# linearSensor.net
KiCad netlist of a schematic drawn in EAGLE
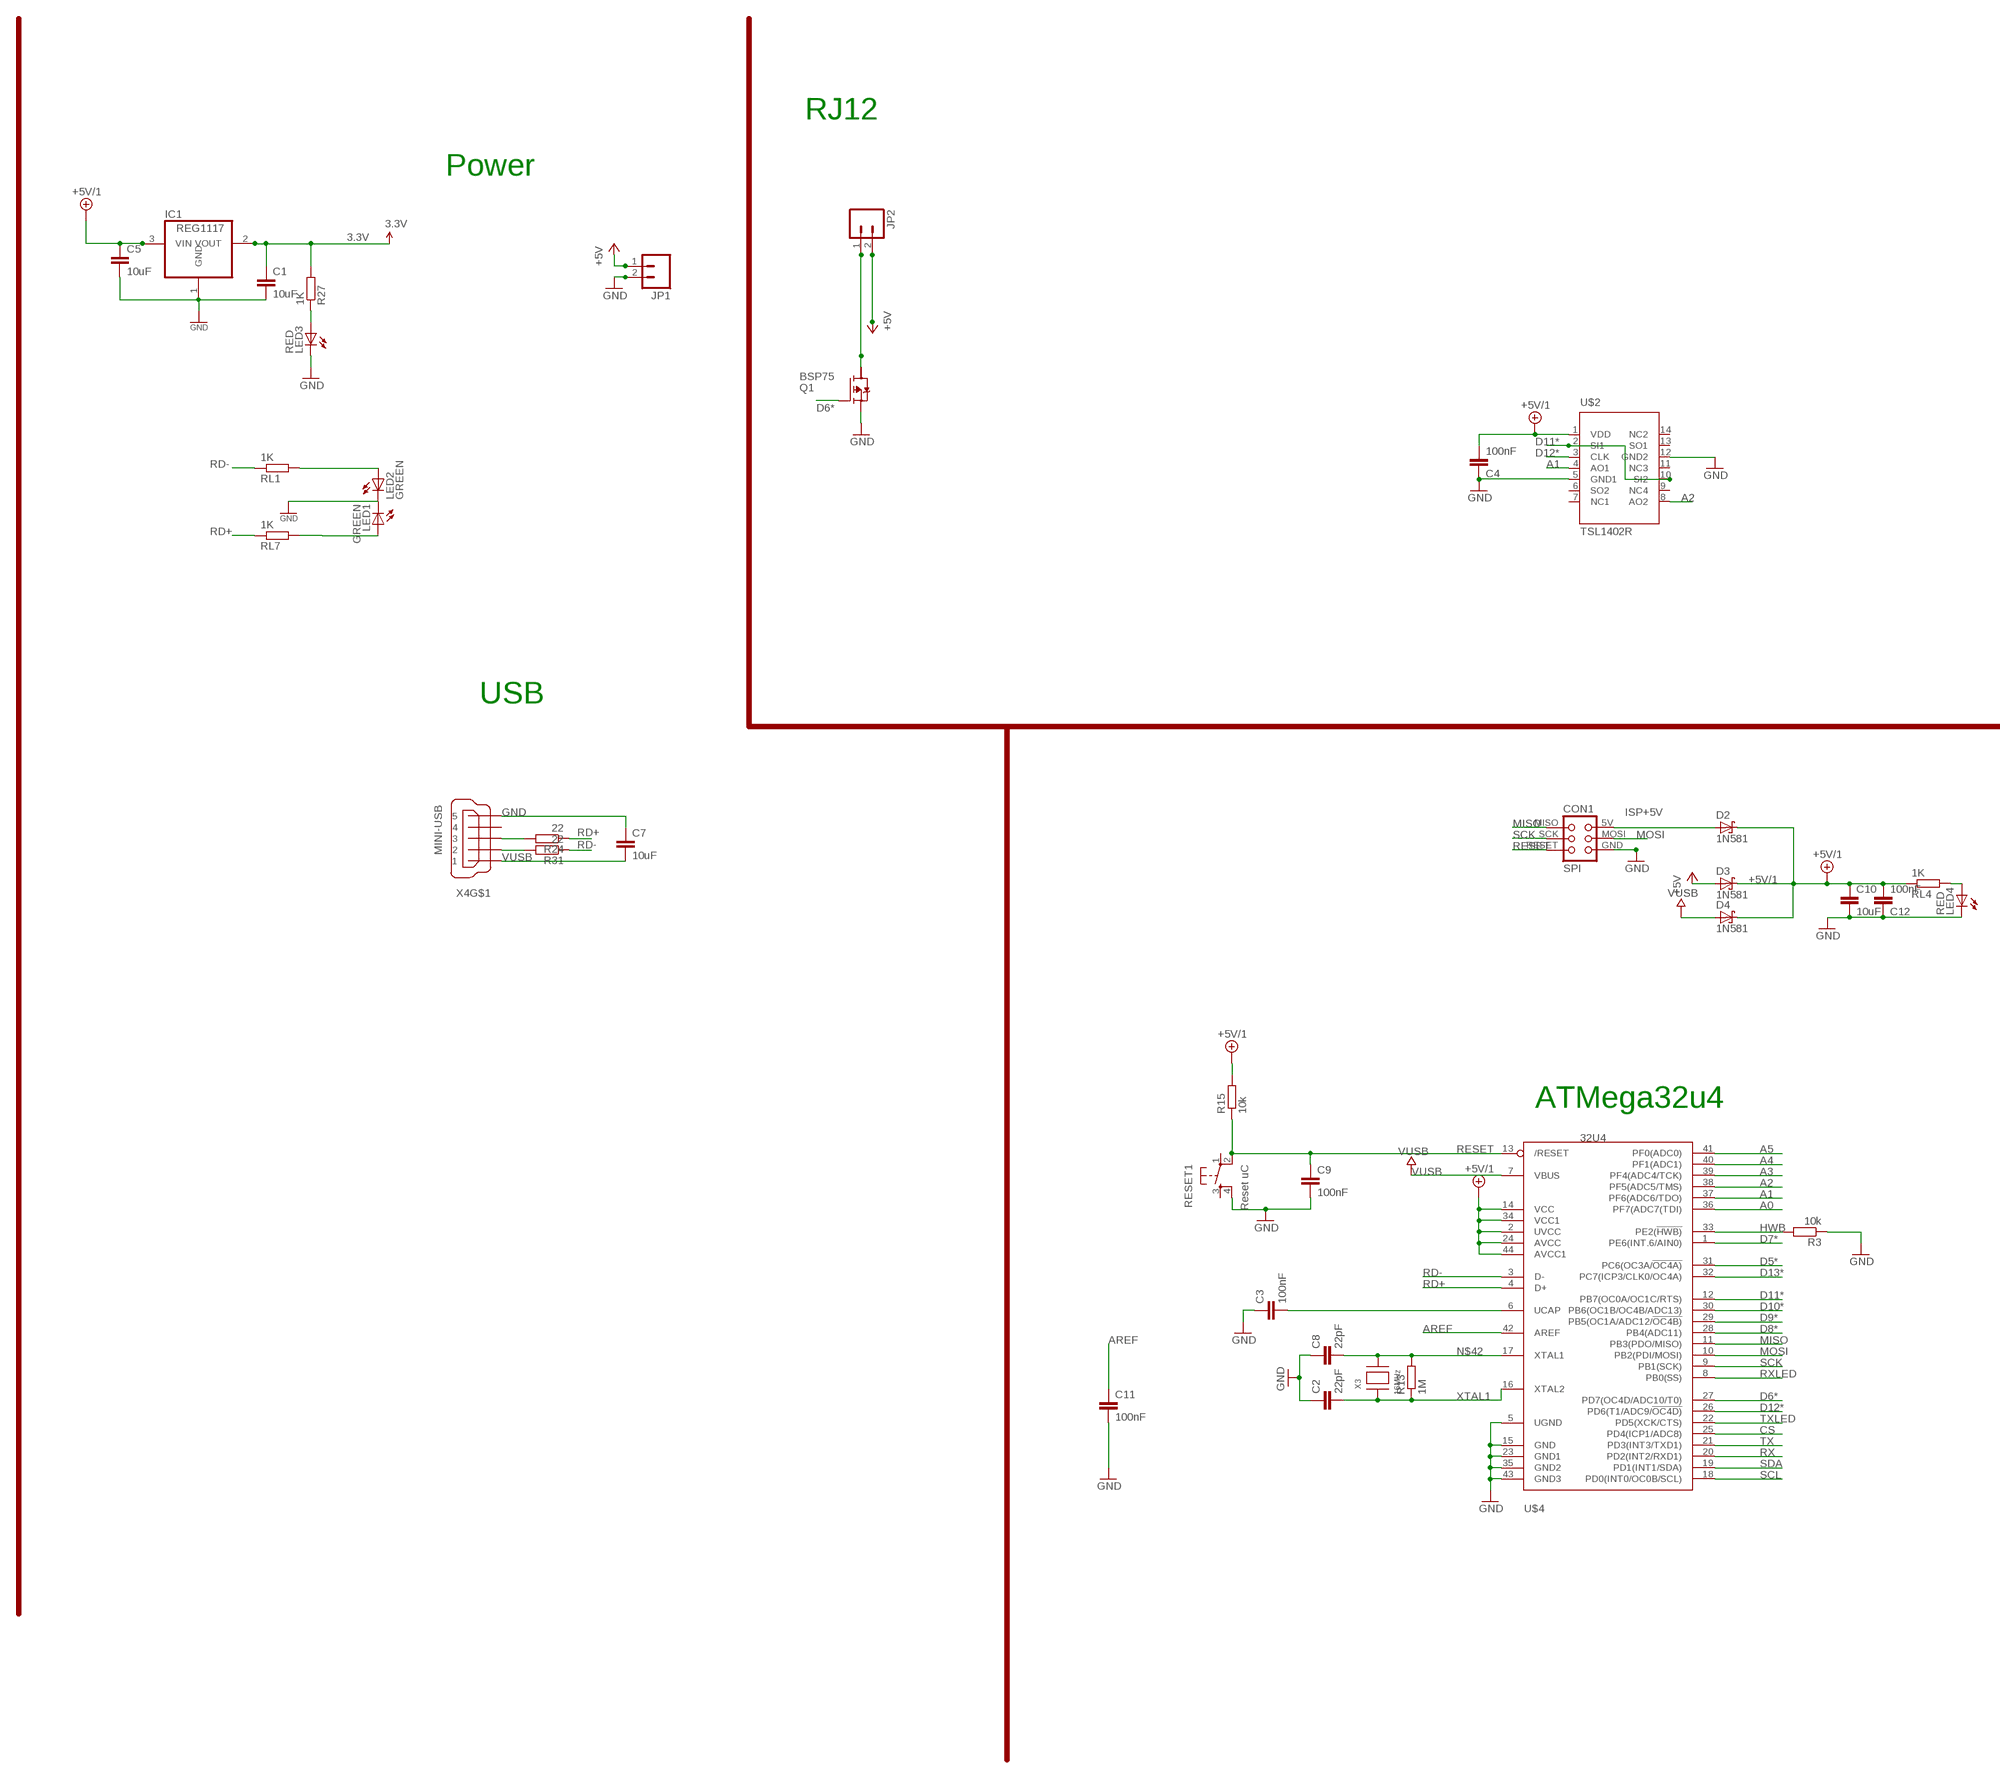
[diagram p0: schematic, sheet 1, part 1 of 2]
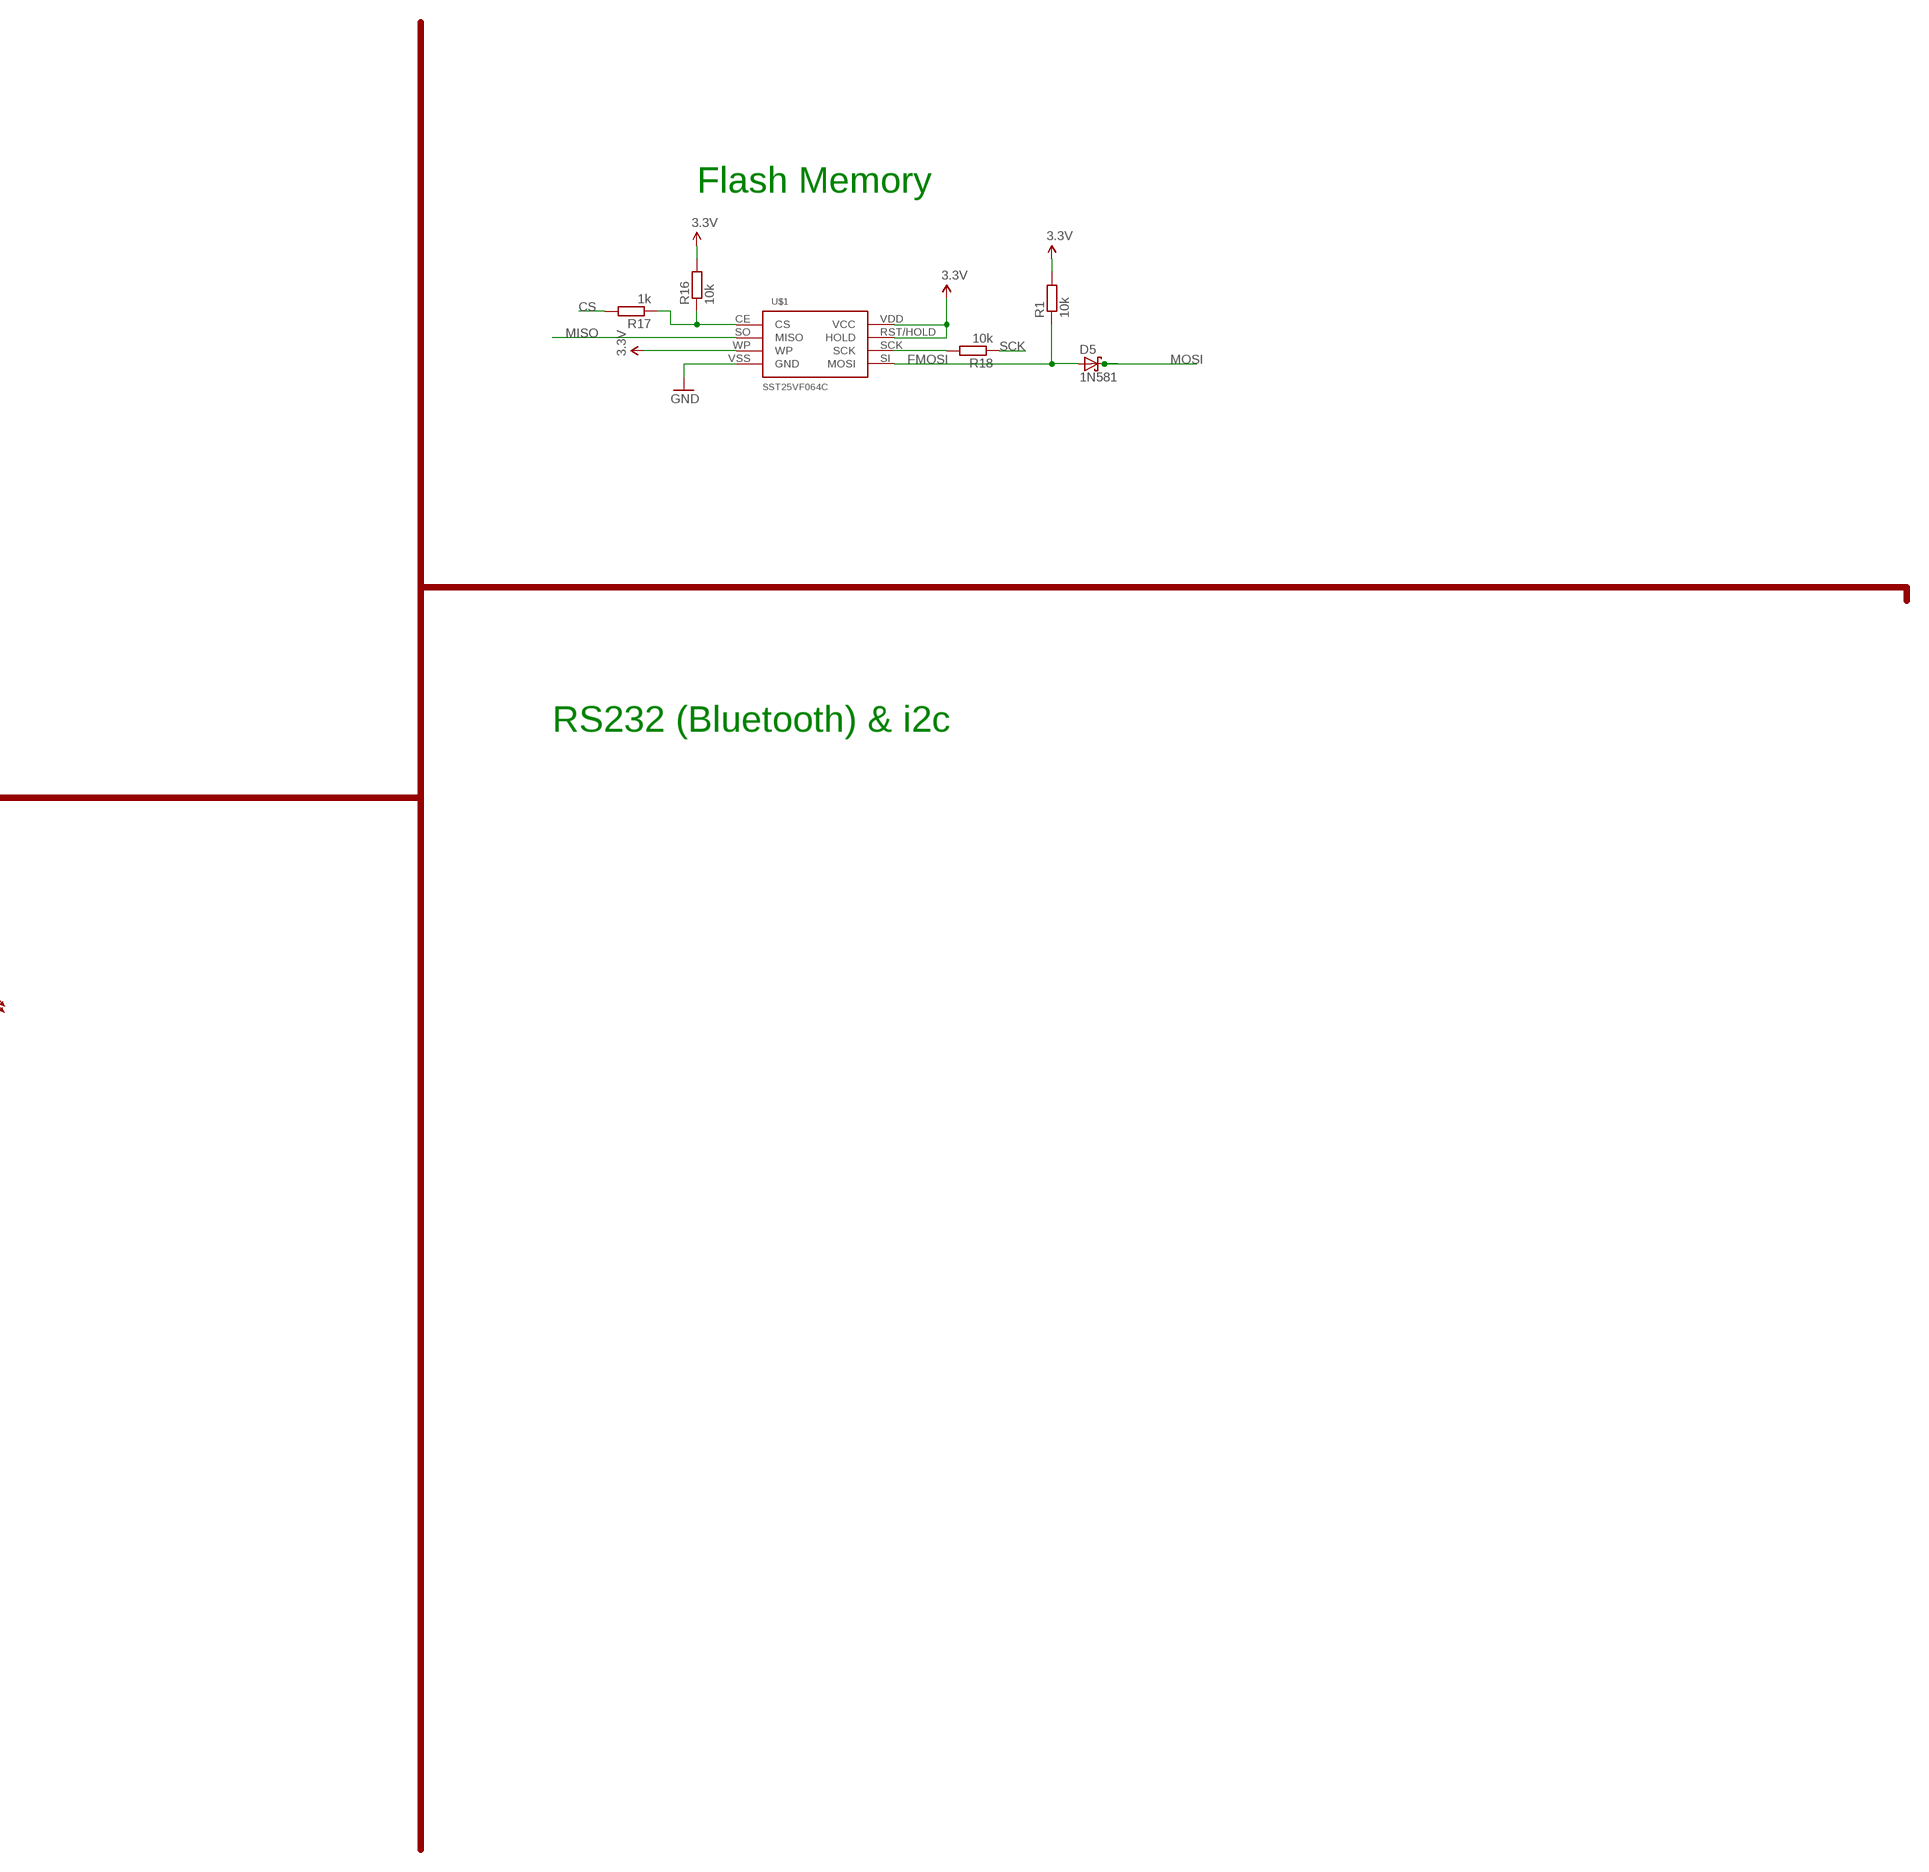
[diagram p1: schematic, sheet 1, part 2 of 2]

(export (version "E")
  (design (tool "Eeschema 10.0.6"))
  (components
    (comp (ref "C1")
      (value "10uF")
      (footprint "eagle-import:C1206")
      (libsource (lib "eagle-import") (part "C-EUC1206"))
    )
    (comp (ref "C2")
      (value "22pF")
      (footprint "eagle-import:C1206")
      (libsource (lib "eagle-import") (part "C-EUC1206"))
    )
    (comp (ref "C3")
      (value "100nF")
      (footprint "eagle-import:C1206")
      (libsource (lib "eagle-import") (part "C-EUC1206"))
    )
    (comp (ref "C4")
      (value "100nF")
      (footprint "eagle-import:C1206")
      (libsource (lib "eagle-import") (part "C-EUC1206"))
    )
    (comp (ref "C5")
      (value "10uF")
      (footprint "eagle-import:C1206")
      (libsource (lib "eagle-import") (part "C-EUC1206"))
    )
    (comp (ref "C7")
      (value "10uF")
      (footprint "eagle-import:C1206")
      (libsource (lib "eagle-import") (part "C-EUC1206"))
    )
    (comp (ref "C8")
      (value "22pF")
      (footprint "eagle-import:C1206")
      (libsource (lib "eagle-import") (part "C-EUC1206"))
    )
    (comp (ref "C9")
      (value "100nF")
      (footprint "eagle-import:C1206")
      (libsource (lib "eagle-import") (part "C-EUC1206"))
    )
    (comp (ref "C10")
      (value "10uF")
      (footprint "eagle-import:C1206")
      (libsource (lib "eagle-import") (part "C-EUC1206"))
    )
    (comp (ref "C11")
      (value "100nF")
      (footprint "eagle-import:C1206")
      (libsource (lib "eagle-import") (part "C-EUC1206"))
    )
    (comp (ref "C12")
      (value "100nF")
      (footprint "eagle-import:C1206")
      (libsource (lib "eagle-import") (part "C-EUC1206"))
    )
    (comp (ref "CON1")
      (value "SPI")
      (footprint "eagle-import:TC2030-MCP-NL")
      (libsource (lib "eagle-import") (part "TINYISPT"))
    )
    (comp (ref "D2")
      (value "1N581")
      (footprint "eagle-import:LED-1206")
      (libsource (lib "eagle-import") (part "1N581D1206"))
    )
    (comp (ref "D3")
      (value "1N581")
      (footprint "eagle-import:LED-1206")
      (libsource (lib "eagle-import") (part "1N581D1206"))
    )
    (comp (ref "D4")
      (value "1N581")
      (footprint "eagle-import:LED-1206")
      (libsource (lib "eagle-import") (part "1N581D1206"))
    )
    (comp (ref "D5")
      (value "1N581")
      (footprint "eagle-import:LED-1206")
      (libsource (lib "eagle-import") (part "1N581D1206"))
    )
    (comp (ref "IC1")
      (value "REG1117")
      (footprint "eagle-import:SOT223")
      (libsource (lib "eagle-import") (part "REG1117"))
    )
    (comp (ref "JP1")
      (value "M02LOCK_LONGPADS")
      (footprint "eagle-import:1X02_LOCK_LONGPADS")
      (libsource (lib "eagle-import") (part "M02LOCK_LONGPADS"))
    )
    (comp (ref "JP2")
      (value "M02LOCK_LONGPADS")
      (footprint "eagle-import:1X02_LOCK_LONGPADS")
      (libsource (lib "eagle-import") (part "M02LOCK_LONGPADS"))
    )
    (comp (ref "LED1")
      (value "GREEN")
      (footprint "eagle-import:CHIP-LED0805")
      (libsource (lib "eagle-import") (part "LEDCHIP-LED0805"))
    )
    (comp (ref "LED2")
      (value "GREEN")
      (footprint "eagle-import:CHIP-LED0805")
      (libsource (lib "eagle-import") (part "LEDCHIP-LED0805"))
    )
    (comp (ref "LED3")
      (value "RED")
      (footprint "eagle-import:CHIP-LED0805")
      (libsource (lib "eagle-import") (part "LEDCHIP-LED0805"))
    )
    (comp (ref "LED4")
      (value "RED")
      (footprint "eagle-import:CHIP-LED0805")
      (libsource (lib "eagle-import") (part "LEDCHIP-LED0805"))
    )
    (comp (ref "Q1")
      (value "BSP75")
      (footprint "eagle-import:PG-SOT-223")
      (libsource (lib "eagle-import") (part "BSP613P"))
    )
    (comp (ref "R1")
      (value "10k")
      (footprint "eagle-import:R1206")
      (libsource (lib "eagle-import") (part "R-EU_R1206"))
    )
    (comp (ref "R3")
      (value "10k")
      (footprint "eagle-import:M0805")
      (libsource (lib "eagle-import") (part "resistor_R-EU_M0805"))
    )
    (comp (ref "R13")
      (value "1M")
      (footprint "eagle-import:R1206")
      (libsource (lib "eagle-import") (part "R-EU_R1206"))
    )
    (comp (ref "R15")
      (value "10k")
      (footprint "eagle-import:M0805")
      (libsource (lib "eagle-import") (part "resistor_R-EU_M0805"))
    )
    (comp (ref "R16")
      (value "10k")
      (footprint "eagle-import:R1206")
      (libsource (lib "eagle-import") (part "R-EU_R1206"))
    )
    (comp (ref "R17")
      (value "1k")
      (footprint "eagle-import:R0805")
      (libsource (lib "eagle-import") (part "R-EU_R0805"))
    )
    (comp (ref "R18")
      (value "10k")
      (footprint "eagle-import:R1206")
      (libsource (lib "eagle-import") (part "R-EU_R1206"))
    )
    (comp (ref "R24")
      (value "22")
      (footprint "eagle-import:M1206")
      (libsource (lib "eagle-import") (part "resistor_R-EU_M1206"))
    )
    (comp (ref "R27")
      (value "1K")
      (footprint "eagle-import:R0805")
      (libsource (lib "eagle-import") (part "R-EU_R0805"))
    )
    (comp (ref "R31")
      (value "22")
      (footprint "eagle-import:M1206")
      (libsource (lib "eagle-import") (part "resistor_R-EU_M1206"))
    )
    (comp (ref "RESET1")
      (value "Reset uC")
      (footprint "eagle-import:TACTILE_SWITCH_SMD")
      (libsource (lib "eagle-import") (part "TAC_SWITCHSMD"))
    )
    (comp (ref "RL1")
      (value "1K")
      (footprint "eagle-import:R0805")
      (libsource (lib "eagle-import") (part "R-EU_R0805"))
    )
    (comp (ref "RL4")
      (value "1K")
      (footprint "eagle-import:R0805")
      (libsource (lib "eagle-import") (part "resistor_R-EU_R0805"))
    )
    (comp (ref "RL7")
      (value "1K")
      (footprint "eagle-import:R0805")
      (libsource (lib "eagle-import") (part "R-EU_R0805"))
    )
    (comp (ref "U$1")
      (value "SST25VF064C")
      (footprint "eagle-import:SOIC_8-LEAD")
      (libsource (lib "eagle-import") (part "SST25VF064C"))
    )
    (comp (ref "U$2")
      (value "TSL1402R")
      (footprint "eagle-import:DIL14")
      (libsource (lib "eagle-import") (part "TSL1402R"))
    )
    (comp (ref "U$4")
      (value "32U4")
      (footprint "eagle-import:TQFP44")
      (libsource (lib "eagle-import") (part "ATMEGA32U4-AU"))
    )
    (comp (ref "X3")
      (value "16MHz")
      (footprint "eagle-import:NX6035")
      (libsource (lib "eagle-import") (part "XTALNX6035"))
    )
    (comp (ref "X4")
      (value "MINI-USB")
      (footprint "eagle-import:32005-201")
      (libsource (lib "eagle-import") (part "MINI-USB-SCHIELD-32005-201"))
    )
  )
  (nets
    (net (code "1") (name "+5V") (class "Default")
      (node (ref "D3") (pin "A") (pinfunction "A_A") (pintype "passive"))
      (node (ref "JP1") (pin "1") (pinfunction "1_1") (pintype "passive"))
      (node (ref "JP2") (pin "2") (pinfunction "2_2") (pintype "passive"))
    )
    (net (code "2") (name "+5V{slash}1") (class "Default")
      (node (ref "C10") (pin "1") (pinfunction "1_1") (pintype "passive"))
      (node (ref "C12") (pin "2") (pinfunction "2_2") (pintype "passive"))
      (node (ref "C4") (pin "2") (pinfunction "2_2") (pintype "passive"))
      (node (ref "C5") (pin "1") (pinfunction "1_1") (pintype "passive"))
      (node (ref "D2") (pin "C") (pinfunction "C_C") (pintype "passive"))
      (node (ref "D3") (pin "C") (pinfunction "C_C") (pintype "passive"))
      (node (ref "D4") (pin "C") (pinfunction "C_C") (pintype "passive"))
      (node (ref "IC1") (pin "3") (pinfunction "VIN_3") (pintype "input"))
      (node (ref "R15") (pin "2") (pinfunction "2_2") (pintype "passive"))
      (node (ref "RL4") (pin "1") (pinfunction "1_1") (pintype "passive"))
      (node (ref "U$2") (pin "1") (pinfunction "VDD_1") (pintype "power_in"))
      (node (ref "U$4") (pin "14") (pinfunction "VCC_14") (pintype "bidirectional"))
      (node (ref "U$4") (pin "2") (pinfunction "UVCC_2") (pintype "bidirectional"))
      (node (ref "U$4") (pin "24") (pinfunction "AVCC_24") (pintype "bidirectional"))
      (node (ref "U$4") (pin "34") (pinfunction "VCC1_34") (pintype "bidirectional"))
      (node (ref "U$4") (pin "44") (pinfunction "AVCC1_44") (pintype "bidirectional"))
    )
    (net (code "3") (name "/A0") (class "Default")
      (node (ref "U$4") (pin "36") (pinfunction "PF7(ADC7(TDI)_36") (pintype "bidirectional"))
    )
    (net (code "4") (name "/A1") (class "Default")
      (node (ref "U$2") (pin "4") (pinfunction "AO1_4") (pintype "output"))
      (node (ref "U$4") (pin "37") (pinfunction "PF6(ADC6/TDO)_37") (pintype "bidirectional"))
    )
    (net (code "5") (name "/A2") (class "Default")
      (node (ref "U$2") (pin "8") (pinfunction "AO2_8") (pintype "output"))
      (node (ref "U$4") (pin "38") (pinfunction "PF5(ADC5/TMS)_38") (pintype "bidirectional"))
    )
    (net (code "6") (name "/A3") (class "Default")
      (node (ref "U$4") (pin "39") (pinfunction "PF4(ADC4/TCK)_39") (pintype "bidirectional"))
    )
    (net (code "7") (name "/A4") (class "Default")
      (node (ref "U$4") (pin "40") (pinfunction "PF1(ADC1)_40") (pintype "bidirectional"))
    )
    (net (code "8") (name "/A5") (class "Default")
      (node (ref "U$4") (pin "41") (pinfunction "PF0(ADC0)_41") (pintype "bidirectional"))
    )
    (net (code "9") (name "/AREF") (class "Default")
      (node (ref "C11") (pin "1") (pinfunction "1_1") (pintype "passive"))
      (node (ref "U$4") (pin "42") (pinfunction "AREF_42") (pintype "bidirectional"))
    )
    (net (code "10") (name "/CS") (class "Default")
      (node (ref "R17") (pin "2") (pinfunction "2_2") (pintype "passive"))
      (node (ref "U$4") (pin "25") (pinfunction "PD4(ICP1/ADC8)_25") (pintype "bidirectional"))
    )
    (net (code "11") (name "/D5*") (class "Default")
      (node (ref "U$4") (pin "31") (pinfunction "PC6(OC3A/~{OC4A})_31") (pintype "bidirectional"))
    )
    (net (code "12") (name "/D6*") (class "Default")
      (node (ref "Q1") (pin "1") (pinfunction "G_1") (pintype "passive"))
      (node (ref "U$4") (pin "27") (pinfunction "PD7(OC4D/ADC10/T0)_27") (pintype "bidirectional"))
    )
    (net (code "13") (name "/D7*") (class "Default")
      (node (ref "U$4") (pin "1") (pinfunction "PE6(INT.6/AIN0)_1") (pintype "bidirectional"))
    )
    (net (code "14") (name "/D8*") (class "Default")
      (node (ref "U$4") (pin "28") (pinfunction "PB4(ADC11)_28") (pintype "bidirectional"))
    )
    (net (code "15") (name "/D9*") (class "Default")
      (node (ref "U$4") (pin "29") (pinfunction "PB5(OC1A/ADC12/~{OC4B})_29") (pintype "bidirectional"))
    )
    (net (code "16") (name "/D10*") (class "Default")
      (node (ref "U$4") (pin "30") (pinfunction "PB6(OC1B/OC4B/ADC13)_30") (pintype "bidirectional"))
    )
    (net (code "17") (name "/D11*") (class "Default")
      (node (ref "U$2") (pin "10") (pinfunction "SI2_10") (pintype "input"))
      (node (ref "U$2") (pin "2") (pinfunction "SI1_2") (pintype "input"))
      (node (ref "U$4") (pin "12") (pinfunction "PB7(OC0A/OC1C/RTS)_12") (pintype "bidirectional"))
    )
    (net (code "18") (name "/D12*") (class "Default")
      (node (ref "U$2") (pin "3") (pinfunction "CLK_3") (pintype "input"))
      (node (ref "U$4") (pin "26") (pinfunction "PD6(T1/ADC9/~{OC4D})_26") (pintype "bidirectional"))
    )
    (net (code "19") (name "/D13*") (class "Default")
      (node (ref "U$4") (pin "32") (pinfunction "PC7(ICP3/CLK0/OC4A)_32") (pintype "bidirectional"))
    )
    (net (code "20") (name "/FMOSI") (class "Default")
      (node (ref "D5") (pin "A") (pinfunction "A_A") (pintype "passive"))
      (node (ref "R1") (pin "1") (pinfunction "1_1") (pintype "passive"))
      (node (ref "U$1") (pin "SI") (pinfunction "MOSI_SI") (pintype "bidirectional"))
    )
    (net (code "21") (name "/HWB") (class "Default")
      (node (ref "R3") (pin "2") (pinfunction "2_2") (pintype "passive"))
      (node (ref "U$4") (pin "33") (pinfunction "PE2(~{HWB})_33") (pintype "bidirectional"))
    )
    (net (code "22") (name "/ISP+5V") (class "Default")
      (node (ref "CON1") (pin "5V") (pinfunction "VCC_5V") (pintype "passive"))
      (node (ref "D2") (pin "A") (pinfunction "A_A") (pintype "passive"))
    )
    (net (code "23") (name "/MISO") (class "Default")
      (node (ref "CON1") (pin "MISO") (pinfunction "MISO_MISO") (pintype "passive"))
      (node (ref "U$1") (pin "SO") (pinfunction "MISO_SO") (pintype "bidirectional"))
      (node (ref "U$4") (pin "11") (pinfunction "PB3(PDO/MISO)_11") (pintype "bidirectional"))
    )
    (net (code "24") (name "/MOSI") (class "Default")
      (node (ref "CON1") (pin "MOSI") (pinfunction "MOSI_MOSI") (pintype "passive"))
      (node (ref "D5") (pin "C") (pinfunction "C_C") (pintype "passive"))
      (node (ref "U$4") (pin "10") (pinfunction "PB2(PDI/MOSI)_10") (pintype "bidirectional"))
    )
    (net (code "25") (name "/N$42") (class "Default")
      (node (ref "C8") (pin "2") (pinfunction "2_2") (pintype "passive"))
      (node (ref "R13") (pin "2") (pinfunction "2_2") (pintype "passive"))
      (node (ref "U$4") (pin "17") (pinfunction "XTAL1_17") (pintype "bidirectional"))
      (node (ref "X3") (pin "P$2") (pinfunction "P$2_P$2") (pintype "bidirectional"))
    )
    (net (code "26") (name "/RD+") (class "Default")
      (node (ref "R24") (pin "1") (pinfunction "1_1") (pintype "passive"))
      (node (ref "RL7") (pin "1") (pinfunction "1_1") (pintype "passive"))
      (node (ref "U$4") (pin "4") (pinfunction "D+_4") (pintype "bidirectional"))
    )
    (net (code "27") (name "/RD-") (class "Default")
      (node (ref "R31") (pin "1") (pinfunction "1_1") (pintype "passive"))
      (node (ref "RL1") (pin "1") (pinfunction "1_1") (pintype "passive"))
      (node (ref "U$4") (pin "3") (pinfunction "D-_3") (pintype "bidirectional"))
    )
    (net (code "28") (name "/RESET") (class "Default")
      (node (ref "C9") (pin "1") (pinfunction "1_1") (pintype "passive"))
      (node (ref "CON1") (pin "RESET") (pinfunction "RESET_RESET") (pintype "passive"))
      (node (ref "R15") (pin "1") (pinfunction "1_1") (pintype "passive"))
      (node (ref "RESET1") (pin "2") (pinfunction "2_2") (pintype "passive"))
      (node (ref "U$4") (pin "13") (pinfunction "/RESET_13") (pintype "bidirectional"))
    )
    (net (code "29") (name "/RX") (class "Default")
      (node (ref "U$4") (pin "20") (pinfunction "PD2(INT2/RXD1)_20") (pintype "bidirectional"))
    )
    (net (code "30") (name "/RXLED") (class "Default")
      (node (ref "U$4") (pin "8") (pinfunction "PB0(SS)_8") (pintype "bidirectional"))
    )
    (net (code "31") (name "/SCK") (class "Default")
      (node (ref "CON1") (pin "SCK") (pinfunction "SCK_SCK") (pintype "passive"))
      (node (ref "R18") (pin "1") (pinfunction "1_1") (pintype "passive"))
      (node (ref "U$4") (pin "9") (pinfunction "PB1(SCK)_9") (pintype "bidirectional"))
    )
    (net (code "32") (name "/SCL") (class "Default")
      (node (ref "U$4") (pin "18") (pinfunction "PD0(INT0/OC0B/SCL)_18") (pintype "bidirectional"))
    )
    (net (code "33") (name "/SDA") (class "Default")
      (node (ref "U$4") (pin "19") (pinfunction "PD1(INT1/SDA)_19") (pintype "bidirectional"))
    )
    (net (code "34") (name "/TX") (class "Default")
      (node (ref "U$4") (pin "21") (pinfunction "PD3(INT3/TXD1)_21") (pintype "bidirectional"))
    )
    (net (code "35") (name "/TXLED") (class "Default")
      (node (ref "U$4") (pin "22") (pinfunction "PD5(XCK/CTS)_22") (pintype "bidirectional"))
    )
    (net (code "36") (name "/XTAL1") (class "Default")
      (node (ref "C2") (pin "2") (pinfunction "2_2") (pintype "passive"))
      (node (ref "R13") (pin "1") (pinfunction "1_1") (pintype "passive"))
      (node (ref "U$4") (pin "16") (pinfunction "XTAL2_16") (pintype "bidirectional"))
      (node (ref "X3") (pin "P$1") (pinfunction "P$1_P$1") (pintype "bidirectional"))
    )
    (net (code "37") (name "3.3V") (class "Default")
      (node (ref "C1") (pin "1") (pinfunction "1_1") (pintype "passive"))
      (node (ref "IC1") (pin "2") (pinfunction "VOUT_2") (pintype "output"))
      (node (ref "R1") (pin "2") (pinfunction "2_2") (pintype "passive"))
      (node (ref "R16") (pin "2") (pinfunction "2_2") (pintype "passive"))
      (node (ref "R27") (pin "2") (pinfunction "2_2") (pintype "passive"))
      (node (ref "U$1") (pin "RST/HOLD") (pinfunction "HOLD_RST/HOLD") (pintype "bidirectional"))
      (node (ref "U$1") (pin "VDD") (pinfunction "VCC_VDD") (pintype "bidirectional"))
      (node (ref "U$1") (pin "WP") (pinfunction "WP_WP") (pintype "bidirectional"))
    )
    (net (code "38") (name "GND") (class "Default")
      (node (ref "C1") (pin "2") (pinfunction "2_2") (pintype "passive"))
      (node (ref "C10") (pin "2") (pinfunction "2_2") (pintype "passive"))
      (node (ref "C11") (pin "2") (pinfunction "2_2") (pintype "passive"))
      (node (ref "C12") (pin "1") (pinfunction "1_1") (pintype "passive"))
      (node (ref "C2") (pin "1") (pinfunction "1_1") (pintype "passive"))
      (node (ref "C3") (pin "1") (pinfunction "1_1") (pintype "passive"))
      (node (ref "C4") (pin "1") (pinfunction "1_1") (pintype "passive"))
      (node (ref "C5") (pin "2") (pinfunction "2_2") (pintype "passive"))
      (node (ref "C7") (pin "1") (pinfunction "1_1") (pintype "passive"))
      (node (ref "C8") (pin "1") (pinfunction "1_1") (pintype "passive"))
      (node (ref "C9") (pin "2") (pinfunction "2_2") (pintype "passive"))
      (node (ref "CON1") (pin "GND") (pinfunction "GND_GND") (pintype "passive"))
      (node (ref "IC1") (pin "1") (pinfunction "GND_1") (pintype "power_in"))
      (node (ref "JP1") (pin "2") (pinfunction "2_2") (pintype "passive"))
      (node (ref "LED1") (pin "C") (pinfunction "C_C") (pintype "passive"))
      (node (ref "LED2") (pin "C") (pinfunction "C_C") (pintype "passive"))
      (node (ref "LED3") (pin "C") (pinfunction "C_C") (pintype "passive"))
      (node (ref "LED4") (pin "C") (pinfunction "C_C") (pintype "passive"))
      (node (ref "Q1") (pin "3") (pinfunction "S_3") (pintype "passive"))
      (node (ref "R3") (pin "1") (pinfunction "1_1") (pintype "passive"))
      (node (ref "RESET1") (pin "4") (pinfunction "4_4") (pintype "passive"))
      (node (ref "U$1") (pin "VSS") (pinfunction "GND_VSS") (pintype "bidirectional"))
      (node (ref "U$2") (pin "12") (pinfunction "GND2_12") (pintype "power_in"))
      (node (ref "U$2") (pin "5") (pinfunction "GND1_5") (pintype "power_in"))
      (node (ref "U$4") (pin "15") (pinfunction "GND_15") (pintype "bidirectional"))
      (node (ref "U$4") (pin "23") (pinfunction "GND1_23") (pintype "bidirectional"))
      (node (ref "U$4") (pin "35") (pinfunction "GND2_35") (pintype "bidirectional"))
      (node (ref "U$4") (pin "43") (pinfunction "GND3_43") (pintype "bidirectional"))
      (node (ref "U$4") (pin "5") (pinfunction "UGND_5") (pintype "bidirectional"))
      (node (ref "X4") (pin "5") (pinfunction "5_5") (pintype "passive"))
    )
    (net (code "39") (name "Net-(JP2-Pad1)") (class "Default")
      (node (ref "JP2") (pin "1") (pinfunction "1_1") (pintype "passive"))
      (node (ref "Q1") (pin "2") (pinfunction "D_2") (pintype "passive"))
    )
    (net (code "40") (name "Net-(LED1-PadA)") (class "Default")
      (node (ref "LED1") (pin "A") (pinfunction "A_A") (pintype "passive"))
      (node (ref "RL7") (pin "2") (pinfunction "2_2") (pintype "passive"))
    )
    (net (code "41") (name "Net-(LED2-PadA)") (class "Default")
      (node (ref "LED2") (pin "A") (pinfunction "A_A") (pintype "passive"))
      (node (ref "RL1") (pin "2") (pinfunction "2_2") (pintype "passive"))
    )
    (net (code "42") (name "Net-(LED3-PadA)") (class "Default")
      (node (ref "LED3") (pin "A") (pinfunction "A_A") (pintype "passive"))
      (node (ref "R27") (pin "1") (pinfunction "1_1") (pintype "passive"))
    )
    (net (code "43") (name "Net-(LED4-PadA)") (class "Default")
      (node (ref "LED4") (pin "A") (pinfunction "A_A") (pintype "passive"))
      (node (ref "RL4") (pin "2") (pinfunction "2_2") (pintype "passive"))
    )
    (net (code "44") (name "Net-(R18-Pad2)") (class "Default")
      (node (ref "R18") (pin "2") (pinfunction "2_2") (pintype "passive"))
      (node (ref "U$1") (pin "SCK") (pinfunction "SCK_SCK") (pintype "bidirectional"))
    )
    (net (code "45") (name "Net-(R24-Pad2)") (class "Default")
      (node (ref "R24") (pin "2") (pinfunction "2_2") (pintype "passive"))
      (node (ref "X4") (pin "3") (pinfunction "3_3") (pintype "passive"))
    )
    (net (code "46") (name "Net-(R31-Pad2)") (class "Default")
      (node (ref "R31") (pin "2") (pinfunction "2_2") (pintype "passive"))
      (node (ref "X4") (pin "2") (pinfunction "2_2") (pintype "passive"))
    )
    (net (code "47") (name "Net-(U$1-CS)") (class "Default")
      (node (ref "R16") (pin "1") (pinfunction "1_1") (pintype "passive"))
      (node (ref "R17") (pin "1") (pinfunction "1_1") (pintype "passive"))
      (node (ref "U$1") (pin "CE") (pinfunction "CS_CE") (pintype "bidirectional"))
    )
    (net (code "48") (name "Net-(U$4-UCAP)") (class "Default")
      (node (ref "C3") (pin "2") (pinfunction "2_2") (pintype "passive"))
      (node (ref "U$4") (pin "6") (pinfunction "UCAP_6") (pintype "bidirectional"))
    )
    (net (code "49") (name "VUSB") (class "Default")
      (node (ref "C7") (pin "2") (pinfunction "2_2") (pintype "passive"))
      (node (ref "D4") (pin "A") (pinfunction "A_A") (pintype "passive"))
      (node (ref "U$4") (pin "7") (pinfunction "VBUS_7") (pintype "bidirectional"))
      (node (ref "X4") (pin "1") (pinfunction "1_1") (pintype "passive"))
    )
    (net (code "50") (name "unconnected-(Q1-D-Pad4)") (class "Default")
      (node (ref "Q1") (pin "4") (pinfunction "D_4") (pintype "passive"))
    )
    (net (code "51") (name "unconnected-(RESET1-Pad1)") (class "Default")
      (node (ref "RESET1") (pin "1") (pinfunction "1_1") (pintype "passive"))
    )
    (net (code "52") (name "unconnected-(RESET1-Pad3)") (class "Default")
      (node (ref "RESET1") (pin "3") (pinfunction "3_3") (pintype "passive"))
    )
    (net (code "53") (name "unconnected-(U$2-NC1-Pad7)") (class "Default")
      (node (ref "U$2") (pin "7") (pinfunction "NC1_7") (pintype "no_connect"))
    )
    (net (code "54") (name "unconnected-(U$2-NC2-Pad14)") (class "Default")
      (node (ref "U$2") (pin "14") (pinfunction "NC2_14") (pintype "no_connect"))
    )
    (net (code "55") (name "unconnected-(U$2-NC3-Pad11)") (class "Default")
      (node (ref "U$2") (pin "11") (pinfunction "NC3_11") (pintype "no_connect"))
    )
    (net (code "56") (name "unconnected-(U$2-NC4-Pad9)") (class "Default")
      (node (ref "U$2") (pin "9") (pinfunction "NC4_9") (pintype "no_connect"))
    )
    (net (code "57") (name "unconnected-(U$2-SO1-Pad13)") (class "Default")
      (node (ref "U$2") (pin "13") (pinfunction "SO1_13") (pintype "output"))
    )
    (net (code "58") (name "unconnected-(U$2-SO2-Pad6)") (class "Default")
      (node (ref "U$2") (pin "6") (pinfunction "SO2_6") (pintype "output"))
    )
    (net (code "59") (name "unconnected-(X4-Pad4)") (class "Default")
      (node (ref "X4") (pin "4") (pinfunction "4_4") (pintype "passive"))
    )
  )
)
